# EMG.net
KiCad netlist of a schematic drawn in EAGLE
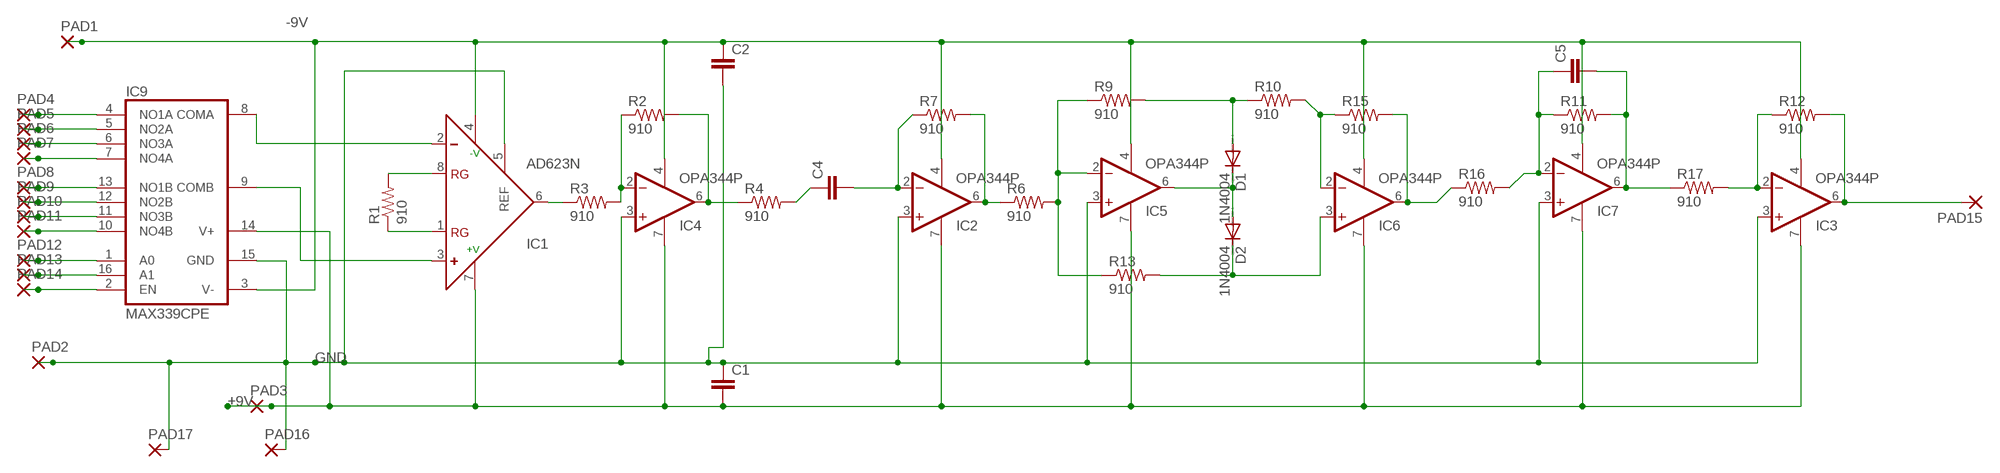
[diagram p0: schematic, sheet 1]

(export (version "E")
  (design (tool "Eeschema 10.0.6"))
  (components
    (comp (ref "C1")
      (value "C2,5-3")
      (footprint "eagle-import:C2.5-3")
      (libsource (lib "eagle-import") (part "C2,5-3"))
    )
    (comp (ref "C2")
      (value "C2,5-3")
      (footprint "eagle-import:C2.5-3")
      (libsource (lib "eagle-import") (part "C2,5-3"))
    )
    (comp (ref "C4")
      (value "C2,5-3")
      (footprint "eagle-import:C2.5-3")
      (libsource (lib "eagle-import") (part "C2,5-3"))
    )
    (comp (ref "C5")
      (value "C2,5-3")
      (footprint "eagle-import:C2.5-3")
      (libsource (lib "eagle-import") (part "C2,5-3"))
    )
    (comp (ref "D1")
      (value "1N4004")
      (footprint "eagle-import:DO41-10")
      (libsource (lib "eagle-import") (part "1N4004"))
    )
    (comp (ref "D2")
      (value "1N4004")
      (footprint "eagle-import:DO41-10")
      (libsource (lib "eagle-import") (part "1N4004"))
    )
    (comp (ref "IC1")
      (value "AD623N")
      (footprint "eagle-import:DIL08")
      (fields (field (name "MF") "ALTERA CORPORATION") (field (name "MPN") "AD623ANZ"))
      (libsource (lib "eagle-import") (part "AD623N"))
    )
    (comp (ref "IC2")
      (value "OPA344P")
      (footprint "eagle-import:DIL08")
      (libsource (lib "eagle-import") (part "OPAP344"))
    )
    (comp (ref "IC3")
      (value "OPA344P")
      (footprint "eagle-import:DIL08")
      (libsource (lib "eagle-import") (part "OPAP344"))
    )
    (comp (ref "IC4")
      (value "OPA344P")
      (footprint "eagle-import:DIL08")
      (libsource (lib "eagle-import") (part "OPAP344"))
    )
    (comp (ref "IC5")
      (value "OPA344P")
      (footprint "eagle-import:DIL08")
      (libsource (lib "eagle-import") (part "OPAP344"))
    )
    (comp (ref "IC6")
      (value "OPA344P")
      (footprint "eagle-import:DIL08")
      (libsource (lib "eagle-import") (part "OPAP344"))
    )
    (comp (ref "IC7")
      (value "OPA344P")
      (footprint "eagle-import:DIL08")
      (libsource (lib "eagle-import") (part "OPAP344"))
    )
    (comp (ref "IC9")
      (value "MAX339CPE")
      (footprint "eagle-import:DIL16")
      (fields (field (name "MPN") "MAX339CPE+"))
      (libsource (lib "eagle-import") (part "MAX339CPE"))
    )
    (comp (ref "PAD1")
      (value "1,6/0,8")
      (footprint "eagle-import:1,6_0,8")
      (libsource (lib "eagle-import") (part "1,6/0,8"))
    )
    (comp (ref "PAD2")
      (value "1,6/0,8")
      (footprint "eagle-import:1,6_0,8")
      (libsource (lib "eagle-import") (part "1,6/0,8"))
    )
    (comp (ref "PAD3")
      (value "1,6/0,8")
      (footprint "eagle-import:1,6_0,8")
      (libsource (lib "eagle-import") (part "1,6/0,8"))
    )
    (comp (ref "PAD4")
      (value "1,6/0,8")
      (footprint "eagle-import:1,6_0,8")
      (libsource (lib "eagle-import") (part "1,6/0,8"))
    )
    (comp (ref "PAD5")
      (value "1,6/0,8")
      (footprint "eagle-import:1,6_0,8")
      (libsource (lib "eagle-import") (part "1,6/0,8"))
    )
    (comp (ref "PAD6")
      (value "1,6/0,8")
      (footprint "eagle-import:1,6_0,8")
      (libsource (lib "eagle-import") (part "1,6/0,8"))
    )
    (comp (ref "PAD7")
      (value "1,6/0,8")
      (footprint "eagle-import:1,6_0,8")
      (libsource (lib "eagle-import") (part "1,6/0,8"))
    )
    (comp (ref "PAD8")
      (value "1,6/0,8")
      (footprint "eagle-import:1,6_0,8")
      (libsource (lib "eagle-import") (part "1,6/0,8"))
    )
    (comp (ref "PAD9")
      (value "1,6/0,8")
      (footprint "eagle-import:1,6_0,8")
      (libsource (lib "eagle-import") (part "1,6/0,8"))
    )
    (comp (ref "PAD10")
      (value "1,6/0,8")
      (footprint "eagle-import:1,6_0,8")
      (libsource (lib "eagle-import") (part "1,6/0,8"))
    )
    (comp (ref "PAD11")
      (value "1,6/0,8")
      (footprint "eagle-import:1,6_0,8")
      (libsource (lib "eagle-import") (part "1,6/0,8"))
    )
    (comp (ref "PAD12")
      (value "1,6/0,8")
      (footprint "eagle-import:1,6_0,8")
      (libsource (lib "eagle-import") (part "1,6/0,8"))
    )
    (comp (ref "PAD13")
      (value "1,6/0,8")
      (footprint "eagle-import:1,6_0,8")
      (libsource (lib "eagle-import") (part "1,6/0,8"))
    )
    (comp (ref "PAD14")
      (value "1,6/0,8")
      (footprint "eagle-import:1,6_0,8")
      (libsource (lib "eagle-import") (part "1,6/0,8"))
    )
    (comp (ref "PAD15")
      (value "1,6/0,8")
      (footprint "eagle-import:1,6_0,8")
      (libsource (lib "eagle-import") (part "1,6/0,8"))
    )
    (comp (ref "PAD16")
      (value "1,6/0,8")
      (footprint "eagle-import:1,6_0,8")
      (libsource (lib "eagle-import") (part "1,6/0,8"))
    )
    (comp (ref "PAD17")
      (value "1,6/0,8")
      (footprint "eagle-import:1,6_0,8")
      (libsource (lib "eagle-import") (part "1,6/0,8"))
    )
    (comp (ref "R1")
      (value "910")
      (footprint "eagle-import:0204_7")
      (libsource (lib "eagle-import") (part "R-US_0204/7"))
    )
    (comp (ref "R2")
      (value "910")
      (footprint "eagle-import:0204_7")
      (libsource (lib "eagle-import") (part "R-US_0204/7"))
    )
    (comp (ref "R3")
      (value "910")
      (footprint "eagle-import:0204_7")
      (libsource (lib "eagle-import") (part "R-US_0204/7"))
    )
    (comp (ref "R4")
      (value "910")
      (footprint "eagle-import:0204_7")
      (libsource (lib "eagle-import") (part "R-US_0204/7"))
    )
    (comp (ref "R6")
      (value "910")
      (footprint "eagle-import:0204_7")
      (libsource (lib "eagle-import") (part "R-US_0204/7"))
    )
    (comp (ref "R7")
      (value "910")
      (footprint "eagle-import:0204_7")
      (libsource (lib "eagle-import") (part "R-US_0204/7"))
    )
    (comp (ref "R9")
      (value "910")
      (footprint "eagle-import:0204_7")
      (libsource (lib "eagle-import") (part "R-US_0204/7"))
    )
    (comp (ref "R10")
      (value "910")
      (footprint "eagle-import:0204_7")
      (libsource (lib "eagle-import") (part "R-US_0204/7"))
    )
    (comp (ref "R11")
      (value "910")
      (footprint "eagle-import:0204_7")
      (libsource (lib "eagle-import") (part "R-US_0204/7"))
    )
    (comp (ref "R12")
      (value "910")
      (footprint "eagle-import:0204_7")
      (libsource (lib "eagle-import") (part "R-US_0204/7"))
    )
    (comp (ref "R13")
      (value "910")
      (footprint "eagle-import:0204_7")
      (libsource (lib "eagle-import") (part "R-US_0204/7"))
    )
    (comp (ref "R15")
      (value "910")
      (footprint "eagle-import:0204_7")
      (libsource (lib "eagle-import") (part "R-US_0204/7"))
    )
    (comp (ref "R16")
      (value "910")
      (footprint "eagle-import:0204_7")
      (libsource (lib "eagle-import") (part "R-US_0204/7"))
    )
    (comp (ref "R17")
      (value "910")
      (footprint "eagle-import:0204_7")
      (libsource (lib "eagle-import") (part "R-US_0204/7"))
    )
  )
  (nets
    (net (code "1") (name "/+9V") (class "Default")
      (node (ref "C1") (pin "2") (pinfunction "2_2") (pintype "passive"))
      (node (ref "IC1") (pin "7") (pinfunction "+V_7") (pintype "power_in"))
      (node (ref "IC2") (pin "7") (pinfunction "V+_7") (pintype "power_in"))
      (node (ref "IC3") (pin "7") (pinfunction "V+_7") (pintype "power_in"))
      (node (ref "IC4") (pin "7") (pinfunction "V+_7") (pintype "power_in"))
      (node (ref "IC5") (pin "7") (pinfunction "V+_7") (pintype "power_in"))
      (node (ref "IC6") (pin "7") (pinfunction "V+_7") (pintype "power_in"))
      (node (ref "IC7") (pin "7") (pinfunction "V+_7") (pintype "power_in"))
      (node (ref "IC9") (pin "14") (pinfunction "V+_14") (pintype "power_in"))
      (node (ref "PAD3") (pin "1") (pinfunction "P_1") (pintype "passive"))
    )
    (net (code "2") (name "/-9V") (class "Default")
      (node (ref "C2") (pin "1") (pinfunction "1_1") (pintype "passive"))
      (node (ref "IC1") (pin "4") (pinfunction "-V_4") (pintype "power_in"))
      (node (ref "IC2") (pin "4") (pinfunction "V-_4") (pintype "power_in"))
      (node (ref "IC3") (pin "4") (pinfunction "V-_4") (pintype "power_in"))
      (node (ref "IC4") (pin "4") (pinfunction "V-_4") (pintype "power_in"))
      (node (ref "IC5") (pin "4") (pinfunction "V-_4") (pintype "power_in"))
      (node (ref "IC6") (pin "4") (pinfunction "V-_4") (pintype "power_in"))
      (node (ref "IC7") (pin "4") (pinfunction "V-_4") (pintype "power_in"))
      (node (ref "IC9") (pin "3") (pinfunction "V-_3") (pintype "power_in"))
      (node (ref "PAD1") (pin "1") (pinfunction "P_1") (pintype "passive"))
    )
    (net (code "3") (name "/GND") (class "Default")
      (node (ref "C1") (pin "1") (pinfunction "1_1") (pintype "passive"))
      (node (ref "C2") (pin "2") (pinfunction "2_2") (pintype "passive"))
      (node (ref "IC1") (pin "5") (pinfunction "REF_5") (pintype "passive"))
      (node (ref "IC2") (pin "3") (pinfunction "+IN_3") (pintype "input"))
      (node (ref "IC3") (pin "3") (pinfunction "+IN_3") (pintype "input"))
      (node (ref "IC4") (pin "3") (pinfunction "+IN_3") (pintype "input"))
      (node (ref "IC5") (pin "3") (pinfunction "+IN_3") (pintype "input"))
      (node (ref "IC7") (pin "3") (pinfunction "+IN_3") (pintype "input"))
      (node (ref "IC9") (pin "15") (pinfunction "GND_15") (pintype "power_in"))
      (node (ref "PAD16") (pin "1") (pinfunction "P_1") (pintype "passive"))
      (node (ref "PAD17") (pin "1") (pinfunction "P_1") (pintype "passive"))
      (node (ref "PAD2") (pin "1") (pinfunction "P_1") (pintype "passive"))
    )
    (net (code "4") (name "Net-(C4-Pad1)") (class "Default")
      (node (ref "C4") (pin "1") (pinfunction "1_1") (pintype "passive"))
      (node (ref "R4") (pin "2") (pinfunction "2_2") (pintype "passive"))
    )
    (net (code "5") (name "Net-(D1-PadA)") (class "Default")
      (node (ref "D1") (pin "A") (pinfunction "A_A") (pintype "passive"))
      (node (ref "R10") (pin "1") (pinfunction "1_1") (pintype "passive"))
      (node (ref "R9") (pin "2") (pinfunction "2_2") (pintype "passive"))
    )
    (net (code "6") (name "Net-(IC1-+)") (class "Default")
      (node (ref "IC1") (pin "3") (pinfunction "+_3") (pintype "input"))
      (node (ref "IC9") (pin "9") (pinfunction "COMB_9") (pintype "passive"))
    )
    (net (code "7") (name "Net-(IC1--)") (class "Default")
      (node (ref "IC1") (pin "2") (pinfunction "-_2") (pintype "input"))
      (node (ref "IC9") (pin "8") (pinfunction "COMA_8") (pintype "passive"))
    )
    (net (code "8") (name "Net-(IC1-OUT)") (class "Default")
      (node (ref "IC1") (pin "6") (pinfunction "OUT_6") (pintype "output"))
      (node (ref "R3") (pin "1") (pinfunction "1_1") (pintype "passive"))
    )
    (net (code "9") (name "Net-(IC1-RG-Pad1)") (class "Default")
      (node (ref "IC1") (pin "1") (pinfunction "RG_1") (pintype "passive"))
      (node (ref "R1") (pin "1") (pinfunction "1_1") (pintype "passive"))
    )
    (net (code "10") (name "Net-(IC1-RG-Pad8)") (class "Default")
      (node (ref "IC1") (pin "8") (pinfunction "RG_8") (pintype "passive"))
      (node (ref "R1") (pin "2") (pinfunction "2_2") (pintype "passive"))
    )
    (net (code "11") (name "Net-(IC2--IN)") (class "Default")
      (node (ref "C4") (pin "2") (pinfunction "2_2") (pintype "passive"))
      (node (ref "IC2") (pin "2") (pinfunction "-IN_2") (pintype "input"))
      (node (ref "R7") (pin "1") (pinfunction "1_1") (pintype "passive"))
    )
    (net (code "12") (name "Net-(IC2-OUT)") (class "Default")
      (node (ref "IC2") (pin "6") (pinfunction "OUT_6") (pintype "output"))
      (node (ref "R6") (pin "1") (pinfunction "1_1") (pintype "passive"))
      (node (ref "R7") (pin "2") (pinfunction "2_2") (pintype "passive"))
    )
    (net (code "13") (name "Net-(IC3--IN)") (class "Default")
      (node (ref "IC3") (pin "2") (pinfunction "-IN_2") (pintype "input"))
      (node (ref "R12") (pin "1") (pinfunction "1_1") (pintype "passive"))
      (node (ref "R17") (pin "2") (pinfunction "2_2") (pintype "passive"))
    )
    (net (code "14") (name "Net-(IC3-OUT)") (class "Default")
      (node (ref "IC3") (pin "6") (pinfunction "OUT_6") (pintype "output"))
      (node (ref "PAD15") (pin "1") (pinfunction "P_1") (pintype "passive"))
      (node (ref "R12") (pin "2") (pinfunction "2_2") (pintype "passive"))
    )
    (net (code "15") (name "Net-(IC4--IN)") (class "Default")
      (node (ref "IC4") (pin "2") (pinfunction "-IN_2") (pintype "input"))
      (node (ref "R2") (pin "1") (pinfunction "1_1") (pintype "passive"))
      (node (ref "R3") (pin "2") (pinfunction "2_2") (pintype "passive"))
    )
    (net (code "16") (name "Net-(IC4-OUT)") (class "Default")
      (node (ref "IC4") (pin "6") (pinfunction "OUT_6") (pintype "output"))
      (node (ref "R2") (pin "2") (pinfunction "2_2") (pintype "passive"))
      (node (ref "R4") (pin "1") (pinfunction "1_1") (pintype "passive"))
    )
    (net (code "17") (name "Net-(IC5--IN)") (class "Default")
      (node (ref "IC5") (pin "2") (pinfunction "-IN_2") (pintype "input"))
      (node (ref "R13") (pin "1") (pinfunction "1_1") (pintype "passive"))
      (node (ref "R6") (pin "2") (pinfunction "2_2") (pintype "passive"))
      (node (ref "R9") (pin "1") (pinfunction "1_1") (pintype "passive"))
    )
    (net (code "18") (name "Net-(IC5-OUT)") (class "Default")
      (node (ref "D1") (pin "C") (pinfunction "C_C") (pintype "passive"))
      (node (ref "D2") (pin "A") (pinfunction "A_A") (pintype "passive"))
      (node (ref "IC5") (pin "6") (pinfunction "OUT_6") (pintype "output"))
    )
    (net (code "19") (name "Net-(IC6-+IN)") (class "Default")
      (node (ref "D2") (pin "C") (pinfunction "C_C") (pintype "passive"))
      (node (ref "IC6") (pin "3") (pinfunction "+IN_3") (pintype "input"))
      (node (ref "R13") (pin "2") (pinfunction "2_2") (pintype "passive"))
    )
    (net (code "20") (name "Net-(IC6--IN)") (class "Default")
      (node (ref "IC6") (pin "2") (pinfunction "-IN_2") (pintype "input"))
      (node (ref "R10") (pin "2") (pinfunction "2_2") (pintype "passive"))
      (node (ref "R15") (pin "1") (pinfunction "1_1") (pintype "passive"))
    )
    (net (code "21") (name "Net-(IC6-OUT)") (class "Default")
      (node (ref "IC6") (pin "6") (pinfunction "OUT_6") (pintype "output"))
      (node (ref "R15") (pin "2") (pinfunction "2_2") (pintype "passive"))
      (node (ref "R16") (pin "1") (pinfunction "1_1") (pintype "passive"))
    )
    (net (code "22") (name "Net-(IC7--IN)") (class "Default")
      (node (ref "C5") (pin "1") (pinfunction "1_1") (pintype "passive"))
      (node (ref "IC7") (pin "2") (pinfunction "-IN_2") (pintype "input"))
      (node (ref "R11") (pin "1") (pinfunction "1_1") (pintype "passive"))
      (node (ref "R16") (pin "2") (pinfunction "2_2") (pintype "passive"))
    )
    (net (code "23") (name "Net-(IC7-OUT)") (class "Default")
      (node (ref "C5") (pin "2") (pinfunction "2_2") (pintype "passive"))
      (node (ref "IC7") (pin "6") (pinfunction "OUT_6") (pintype "output"))
      (node (ref "R11") (pin "2") (pinfunction "2_2") (pintype "passive"))
      (node (ref "R17") (pin "1") (pinfunction "1_1") (pintype "passive"))
    )
    (net (code "24") (name "Net-(IC9-A0)") (class "Default")
      (node (ref "IC9") (pin "1") (pinfunction "A0_1") (pintype "input"))
      (node (ref "PAD12") (pin "1") (pinfunction "P_1") (pintype "passive"))
    )
    (net (code "25") (name "Net-(IC9-A1)") (class "Default")
      (node (ref "IC9") (pin "16") (pinfunction "A1_16") (pintype "input"))
      (node (ref "PAD13") (pin "1") (pinfunction "P_1") (pintype "passive"))
    )
    (net (code "26") (name "Net-(IC9-EN)") (class "Default")
      (node (ref "IC9") (pin "2") (pinfunction "EN_2") (pintype "input"))
      (node (ref "PAD14") (pin "1") (pinfunction "P_1") (pintype "passive"))
    )
    (net (code "27") (name "Net-(IC9-NO1A)") (class "Default")
      (node (ref "IC9") (pin "4") (pinfunction "NO1A_4") (pintype "passive"))
      (node (ref "PAD4") (pin "1") (pinfunction "P_1") (pintype "passive"))
    )
    (net (code "28") (name "Net-(IC9-NO1B)") (class "Default")
      (node (ref "IC9") (pin "13") (pinfunction "NO1B_13") (pintype "passive"))
      (node (ref "PAD8") (pin "1") (pinfunction "P_1") (pintype "passive"))
    )
    (net (code "29") (name "Net-(IC9-NO2A)") (class "Default")
      (node (ref "IC9") (pin "5") (pinfunction "NO2A_5") (pintype "passive"))
      (node (ref "PAD5") (pin "1") (pinfunction "P_1") (pintype "passive"))
    )
    (net (code "30") (name "Net-(IC9-NO2B)") (class "Default")
      (node (ref "IC9") (pin "12") (pinfunction "NO2B_12") (pintype "passive"))
      (node (ref "PAD9") (pin "1") (pinfunction "P_1") (pintype "passive"))
    )
    (net (code "31") (name "Net-(IC9-NO3A)") (class "Default")
      (node (ref "IC9") (pin "6") (pinfunction "NO3A_6") (pintype "passive"))
      (node (ref "PAD6") (pin "1") (pinfunction "P_1") (pintype "passive"))
    )
    (net (code "32") (name "Net-(IC9-NO3B)") (class "Default")
      (node (ref "IC9") (pin "11") (pinfunction "NO3B_11") (pintype "passive"))
      (node (ref "PAD10") (pin "1") (pinfunction "P_1") (pintype "passive"))
    )
    (net (code "33") (name "Net-(IC9-NO4A)") (class "Default")
      (node (ref "IC9") (pin "7") (pinfunction "NO4A_7") (pintype "passive"))
      (node (ref "PAD7") (pin "1") (pinfunction "P_1") (pintype "passive"))
    )
    (net (code "34") (name "Net-(IC9-NO4B)") (class "Default")
      (node (ref "IC9") (pin "10") (pinfunction "NO4B_10") (pintype "passive"))
      (node (ref "PAD11") (pin "1") (pinfunction "P_1") (pintype "passive"))
    )
  )
)
